# Motor_Ctl.net
KiCad netlist of a schematic drawn in Altium Designer
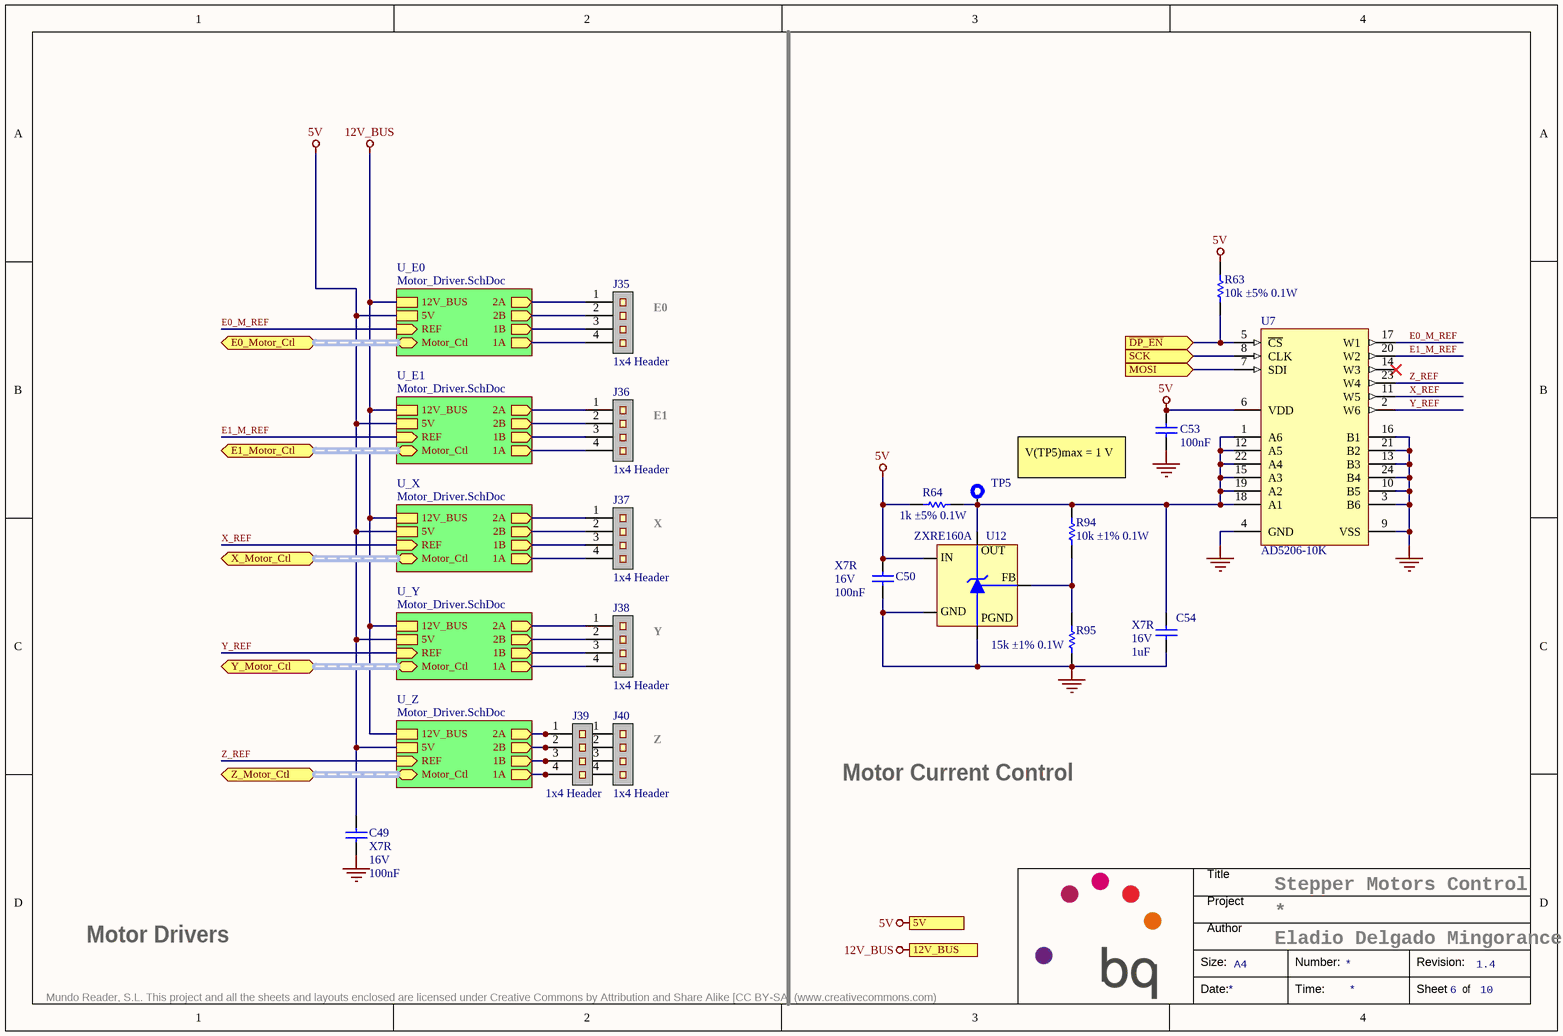
[diagram p0: Motor_Ctl.SchDoc]

(export (version "E")
  (design (tool "Eeschema 10.0.6"))
  (components
    (comp (ref "C49")
      (value "Capacitor")
      (footprint "C0603")
      (description "Capacitor SMD")
      (fields
        (field (name "DIELECTRIC") "X7R")
        (field (name "VOLTAGE") "16V")
        (field (name "CAPACITANCE") "100nF")
        (field (name "PART NUMBER") "C0603_100nF_16V_±10%")
        (field (name "TOLERANCE") "±10%")
      )
      (libsource (lib "Pasives_Capacitor_SMD") (part "Capacitor"))
    )
    (comp (ref "C50")
      (value "Capacitor")
      (footprint "C0603")
      (description "Capacitor SMD")
      (fields
        (field (name "DIELECTRIC") "X7R")
        (field (name "VOLTAGE") "16V")
        (field (name "CAPACITANCE") "100nF")
        (field (name "PART NUMBER") "C0603_100nF_16V_±10%")
        (field (name "TOLERANCE") "±10%")
      )
      (libsource (lib "Pasives_Capacitor_SMD") (part "Capacitor"))
    )
    (comp (ref "C53")
      (value "Capacitor")
      (footprint "C0603")
      (fields
        (field (name "VOLTAGE") "16V")
        (field (name "CAPACITANCE") "100nF")
        (field (name "PART NUMBER") "C0603_100nF_16V_±10%")
        (field (name "TOLERANCE") "±10%")
      )
      (libsource (lib "Pasives_Capacitor_SMD") (part "Capacitor"))
    )
    (comp (ref "C54")
      (value "Capacitor")
      (footprint "C0603")
      (fields
        (field (name "DIELECTRIC") "X7R")
        (field (name "VOLTAGE") "16V")
        (field (name "CAPACITANCE") "1uF")
        (field (name "PART NUMBER") "C0603_1uF_16V_±10%_X7R")
        (field (name "TOLERANCE") "±10%")
        (field (name "MANUFACTURER") "TDK")
      )
      (libsource (lib "Pasives_Capacitor_SMD") (part "Capacitor"))
    )
    (comp (ref "J35")
      (value "1x4 Header")
      (footprint "1x4 MTE Straight Header 2.54mm")
      (description "Connector, 1x4 MTE Straight Header 2.54mm")
      (fields
        (field (name "PART NUMBER") "CON_MTE_HDR_THT2.54_4")
        (field (name "MANUFACTURER") "TE Connectivity")
      )
      (libsource (lib "Conectores_MTE_Header_2.54") (part "1x4 MTE Straight Header 2.54mm"))
    )
    (comp (ref "J36")
      (value "1x4 Header")
      (footprint "1x4 MTE Straight Header 2.54mm")
      (description "Connector, 1x4 MTE Straight Header 2.54mm")
      (fields
        (field (name "PART NUMBER") "CON_MTE_HDR_THT2.54_4")
        (field (name "MANUFACTURER") "TE Connectivity")
      )
      (libsource (lib "Conectores_MTE_Header_2.54") (part "1x4 MTE Straight Header 2.54mm"))
    )
    (comp (ref "J37")
      (value "1x4 Header")
      (footprint "1x4 MTE Straight Header 2.54mm")
      (description "Connector, 1x4 MTE Straight Header 2.54mm")
      (fields
        (field (name "PART NUMBER") "CON_MTE_HDR_THT2.54_4")
        (field (name "MANUFACTURER") "TE Connectivity")
      )
      (libsource (lib "Conectores_MTE_Header_2.54") (part "1x4 MTE Straight Header 2.54mm"))
    )
    (comp (ref "J38")
      (value "1x4 Header")
      (footprint "1x4 MTE Straight Header 2.54mm")
      (description "Connector, 1x4 MTE Straight Header 2.54mm")
      (fields
        (field (name "PART NUMBER") "CON_MTE_HDR_THT2.54_4")
        (field (name "MANUFACTURER") "TE Connectivity")
      )
      (libsource (lib "Conectores_MTE_Header_2.54") (part "1x4 MTE Straight Header 2.54mm"))
    )
    (comp (ref "J39")
      (value "1x4 Header")
      (footprint "1x4 MTE Straight Header 2.54mm")
      (description "Connector, 1x4 MTE Straight Header 2.54mm")
      (fields
        (field (name "PART NUMBER") "CON_MTE_HDR_THT2.54_4")
        (field (name "MANUFACTURER") "TE Connectivity")
      )
      (libsource (lib "Conectores_MTE_Header_2.54") (part "1x4 MTE Straight Header 2.54mm"))
    )
    (comp (ref "J40")
      (value "1x4 Header")
      (footprint "1x4 MTE Straight Header 2.54mm")
      (description "Connector, 1x4 MTE Straight Header 2.54mm")
      (fields
        (field (name "PART NUMBER") "CON_MTE_HDR_THT2.54_4")
        (field (name "MANUFACTURER") "TE Connectivity")
      )
      (libsource (lib "Conectores_MTE_Header_2.54") (part "1x4 MTE Straight Header 2.54mm"))
    )
    (comp (ref "R63")
      (value "10k ±5% 0.1W")
      (footprint "R0603")
      (description "Resistor")
      (fields (field (name "TOLERANCE") "±5%") (field (name "POWER") "0.1W"))
      (libsource (lib "Pasives_Resistor_SMD") (part "Resistor"))
    )
    (comp (ref "R64")
      (value "1k ±5% 0.1W")
      (footprint "R0603")
      (description "Resistor, SMD")
      (fields (field (name "TOLERANCE") "±5%") (field (name "POWER") "0.1W"))
      (libsource (lib "Pasives_Resistor_SMD") (part "Resistor"))
    )
    (comp (ref "R94")
      (value "10k ±1% 0.1W")
      (footprint "R0603")
      (description "Resistor, SMD")
      (fields (field (name "TOLERANCE") "±1%") (field (name "POWER") "0.1W"))
      (libsource (lib "Pasives_Resistor_SMD") (part "Resistor"))
    )
    (comp (ref "R95")
      (value "15k ±1% 0.1W")
      (footprint "R0603")
      (description "Resistor, SMD")
      (fields (field (name "TOLERANCE") "±1%") (field (name "POWER") "0.1W"))
      (libsource (lib "Pasives_Resistor_SMD") (part "Resistor"))
    )
    (comp (ref "TP5")
      (value "Testpoint")
      (footprint "TP_SMD_1mm")
      (fields (field (name "PART NUMBER") "TP_SMD_1mm"))
      (libsource (lib "Miscelanea") (part "Testpoint"))
    )
    (comp (ref "U7")
      (value "AD5206-10K")
      (footprint "TSSOP24_065")
      (description "6-Channel Digital Potentiometer, 10K")
      (fields (field (name "PART NUMBER") "AD5206") (field (name "MANUFACTURER") "Analog Devices"))
      (libsource (lib "Mixed_Signal") (part "AD5206BRUZ10"))
    )
    (comp (ref "U12")
      (value "ZXRE160A")
      (footprint "SOT-353")
      (description "Adjustable Shunt Voltage Regulator")
      (fields (field (name "TOLERANCE") "0,005") (field (name "MANUFACTURER") "Diodes Incorporated"))
      (libsource (lib "Power_Voltage_Reference") (part "Adj Shunt Voltage Reg"))
    )
  )
  (nets
    (net (code "6") (name "/1A") (class "Default")
      (node (ref "J35") (pin "4") (pinfunction "4_4") (pintype "passive"))
    )
    (net (code "7") (name "/1A_1") (class "Default")
      (node (ref "J39") (pin "4") (pinfunction "4_4") (pintype "passive"))
      (node (ref "J40") (pin "4") (pinfunction "4_4") (pintype "passive"))
    )
    (net (code "8") (name "/1A_2") (class "Default")
      (node (ref "J38") (pin "4") (pinfunction "4_4") (pintype "passive"))
    )
    (net (code "9") (name "/1A_3") (class "Default")
      (node (ref "J36") (pin "4") (pinfunction "4_4") (pintype "passive"))
    )
    (net (code "10") (name "/1A_4") (class "Default")
      (node (ref "J37") (pin "4") (pinfunction "4_4") (pintype "passive"))
    )
    (net (code "11") (name "/1B") (class "Default")
      (node (ref "J38") (pin "3") (pinfunction "3_3") (pintype "passive"))
    )
    (net (code "12") (name "/1B_1") (class "Default")
      (node (ref "J39") (pin "3") (pinfunction "3_3") (pintype "passive"))
      (node (ref "J40") (pin "3") (pinfunction "3_3") (pintype "passive"))
    )
    (net (code "13") (name "/1B_2") (class "Default")
      (node (ref "J36") (pin "3") (pinfunction "3_3") (pintype "passive"))
    )
    (net (code "14") (name "/1B_3") (class "Default")
      (node (ref "J37") (pin "3") (pinfunction "3_3") (pintype "passive"))
    )
    (net (code "15") (name "/1B_4") (class "Default")
      (node (ref "J35") (pin "3") (pinfunction "3_3") (pintype "passive"))
    )
    (net (code "16") (name "/2A") (class "Default")
      (node (ref "J38") (pin "1") (pinfunction "1_1") (pintype "passive"))
    )
    (net (code "17") (name "/2A_1") (class "Default")
      (node (ref "J39") (pin "1") (pinfunction "1_1") (pintype "passive"))
      (node (ref "J40") (pin "1") (pinfunction "1_1") (pintype "passive"))
    )
    (net (code "18") (name "/2A_2") (class "Default")
      (node (ref "J36") (pin "1") (pinfunction "1_1") (pintype "passive"))
    )
    (net (code "19") (name "/2A_3") (class "Default")
      (node (ref "J37") (pin "1") (pinfunction "1_1") (pintype "passive"))
    )
    (net (code "20") (name "/2A_4") (class "Default")
      (node (ref "J35") (pin "1") (pinfunction "1_1") (pintype "passive"))
    )
    (net (code "21") (name "/2B") (class "Default")
      (node (ref "J39") (pin "2") (pinfunction "2_2") (pintype "passive"))
      (node (ref "J40") (pin "2") (pinfunction "2_2") (pintype "passive"))
    )
    (net (code "22") (name "/2B_1") (class "Default")
      (node (ref "J36") (pin "2") (pinfunction "2_2") (pintype "passive"))
    )
    (net (code "23") (name "/2B_2") (class "Default")
      (node (ref "J37") (pin "2") (pinfunction "2_2") (pintype "passive"))
    )
    (net (code "24") (name "/2B_3") (class "Default")
      (node (ref "J35") (pin "2") (pinfunction "2_2") (pintype "passive"))
    )
    (net (code "25") (name "/2B_4") (class "Default")
      (node (ref "J38") (pin "2") (pinfunction "2_2") (pintype "passive"))
    )
    (net (code "26") (name "/DP_EN") (class "Default")
      (node (ref "R63") (pin "2") (pinfunction "2_2") (pintype "passive"))
      (node (ref "U7") (pin "5") (pinfunction "CS_5") (pintype "input"))
    )
    (net (code "27") (name "/E0_M_REF") (class "Default")
      (node (ref "U7") (pin "17") (pinfunction "W1_17") (pintype "output"))
    )
    (net (code "29") (name "/E1_M_REF") (class "Default")
      (node (ref "U7") (pin "20") (pinfunction "W2_20") (pintype "output"))
    )
    (net (code "31") (name "/MOSI") (class "Default")
      (node (ref "U7") (pin "7") (pinfunction "SDI_7") (pintype "input"))
    )
    (net (code "32") (name "/SCK") (class "Default")
      (node (ref "U7") (pin "8") (pinfunction "CLK_8") (pintype "input"))
    )
    (net (code "34") (name "/X_REF") (class "Default")
      (node (ref "U7") (pin "11") (pinfunction "W5_11") (pintype "output"))
    )
    (net (code "36") (name "/Y_REF") (class "Default")
      (node (ref "U7") (pin "2") (pinfunction "W6_2") (pintype "output"))
    )
    (net (code "38") (name "/Z_REF") (class "Default")
      (node (ref "U7") (pin "23") (pinfunction "W4_23") (pintype "output"))
    )
    (net (code "39") (name "5V") (class "Default")
      (node (ref "C49") (pin "2") (pinfunction "2_2") (pintype "passive"))
      (node (ref "C50") (pin "2") (pinfunction "2_2") (pintype "passive"))
      (node (ref "C53") (pin "2") (pinfunction "2_2") (pintype "passive"))
      (node (ref "R63") (pin "1") (pinfunction "1_1") (pintype "passive"))
      (node (ref "R64") (pin "2") (pinfunction "2_2") (pintype "passive"))
      (node (ref "U12") (pin "3") (pinfunction "3_3") (pintype "passive"))
      (node (ref "U7") (pin "6") (pinfunction "VDD_6") (pintype "power_in"))
    )
    (net (code "41") (name "GND") (class "Default")
      (node (ref "C49") (pin "1") (pinfunction "1_1") (pintype "passive"))
      (node (ref "C50") (pin "1") (pinfunction "1_1") (pintype "passive"))
      (node (ref "C53") (pin "1") (pinfunction "1_1") (pintype "passive"))
      (node (ref "C54") (pin "1") (pinfunction "1_1") (pintype "passive"))
      (node (ref "R95") (pin "1") (pinfunction "1_1") (pintype "passive"))
      (node (ref "U12") (pin "1") (pinfunction "1_1") (pintype "passive"))
      (node (ref "U12") (pin "2") (pinfunction "2_2") (pintype "passive"))
      (node (ref "U7") (pin "10") (pinfunction "B5_10") (pintype "passive"))
      (node (ref "U7") (pin "13") (pinfunction "B3_13") (pintype "passive"))
      (node (ref "U7") (pin "16") (pinfunction "B1_16") (pintype "passive"))
      (node (ref "U7") (pin "21") (pinfunction "B2_21") (pintype "passive"))
      (node (ref "U7") (pin "24") (pinfunction "B4_24") (pintype "passive"))
      (node (ref "U7") (pin "3") (pinfunction "B6_3") (pintype "passive"))
      (node (ref "U7") (pin "4") (pinfunction "GND_4") (pintype "power_in"))
      (node (ref "U7") (pin "9") (pinfunction "VSS_9") (pintype "power_in"))
    )
    (net (code "42") (name "Net-(R94-Pad1)") (class "Default")
      (node (ref "R94") (pin "1") (pinfunction "1_1") (pintype "passive"))
      (node (ref "R95") (pin "2") (pinfunction "2_2") (pintype "passive"))
      (node (ref "U12") (pin "4") (pinfunction "4_4") (pintype "passive"))
    )
    (net (code "43") (name "Net-(U7-A1)") (class "Default")
      (node (ref "C54") (pin "2") (pinfunction "2_2") (pintype "passive"))
      (node (ref "R64") (pin "1") (pinfunction "1_1") (pintype "passive"))
      (node (ref "R94") (pin "2") (pinfunction "2_2") (pintype "passive"))
      (node (ref "TP5") (pin "1") (pinfunction "1_1") (pintype "passive"))
      (node (ref "U12") (pin "5") (pinfunction "5_5") (pintype "passive"))
      (node (ref "U7") (pin "1") (pinfunction "A6_1") (pintype "passive"))
      (node (ref "U7") (pin "12") (pinfunction "A5_12") (pintype "passive"))
      (node (ref "U7") (pin "15") (pinfunction "A3_15") (pintype "passive"))
      (node (ref "U7") (pin "18") (pinfunction "A1_18") (pintype "passive"))
      (node (ref "U7") (pin "19") (pinfunction "A2_19") (pintype "passive"))
      (node (ref "U7") (pin "22") (pinfunction "A4_22") (pintype "passive"))
    )
    (net (code "44") (name "unconnected-(U7-W3-Pad14)") (class "Default")
      (node (ref "U7") (pin "14") (pinfunction "W3_14") (pintype "output+no_connect"))
    )
  )
)
